# FRA_junctionB_v1.net
KiCad netlist of a schematic drawn in EAGLE
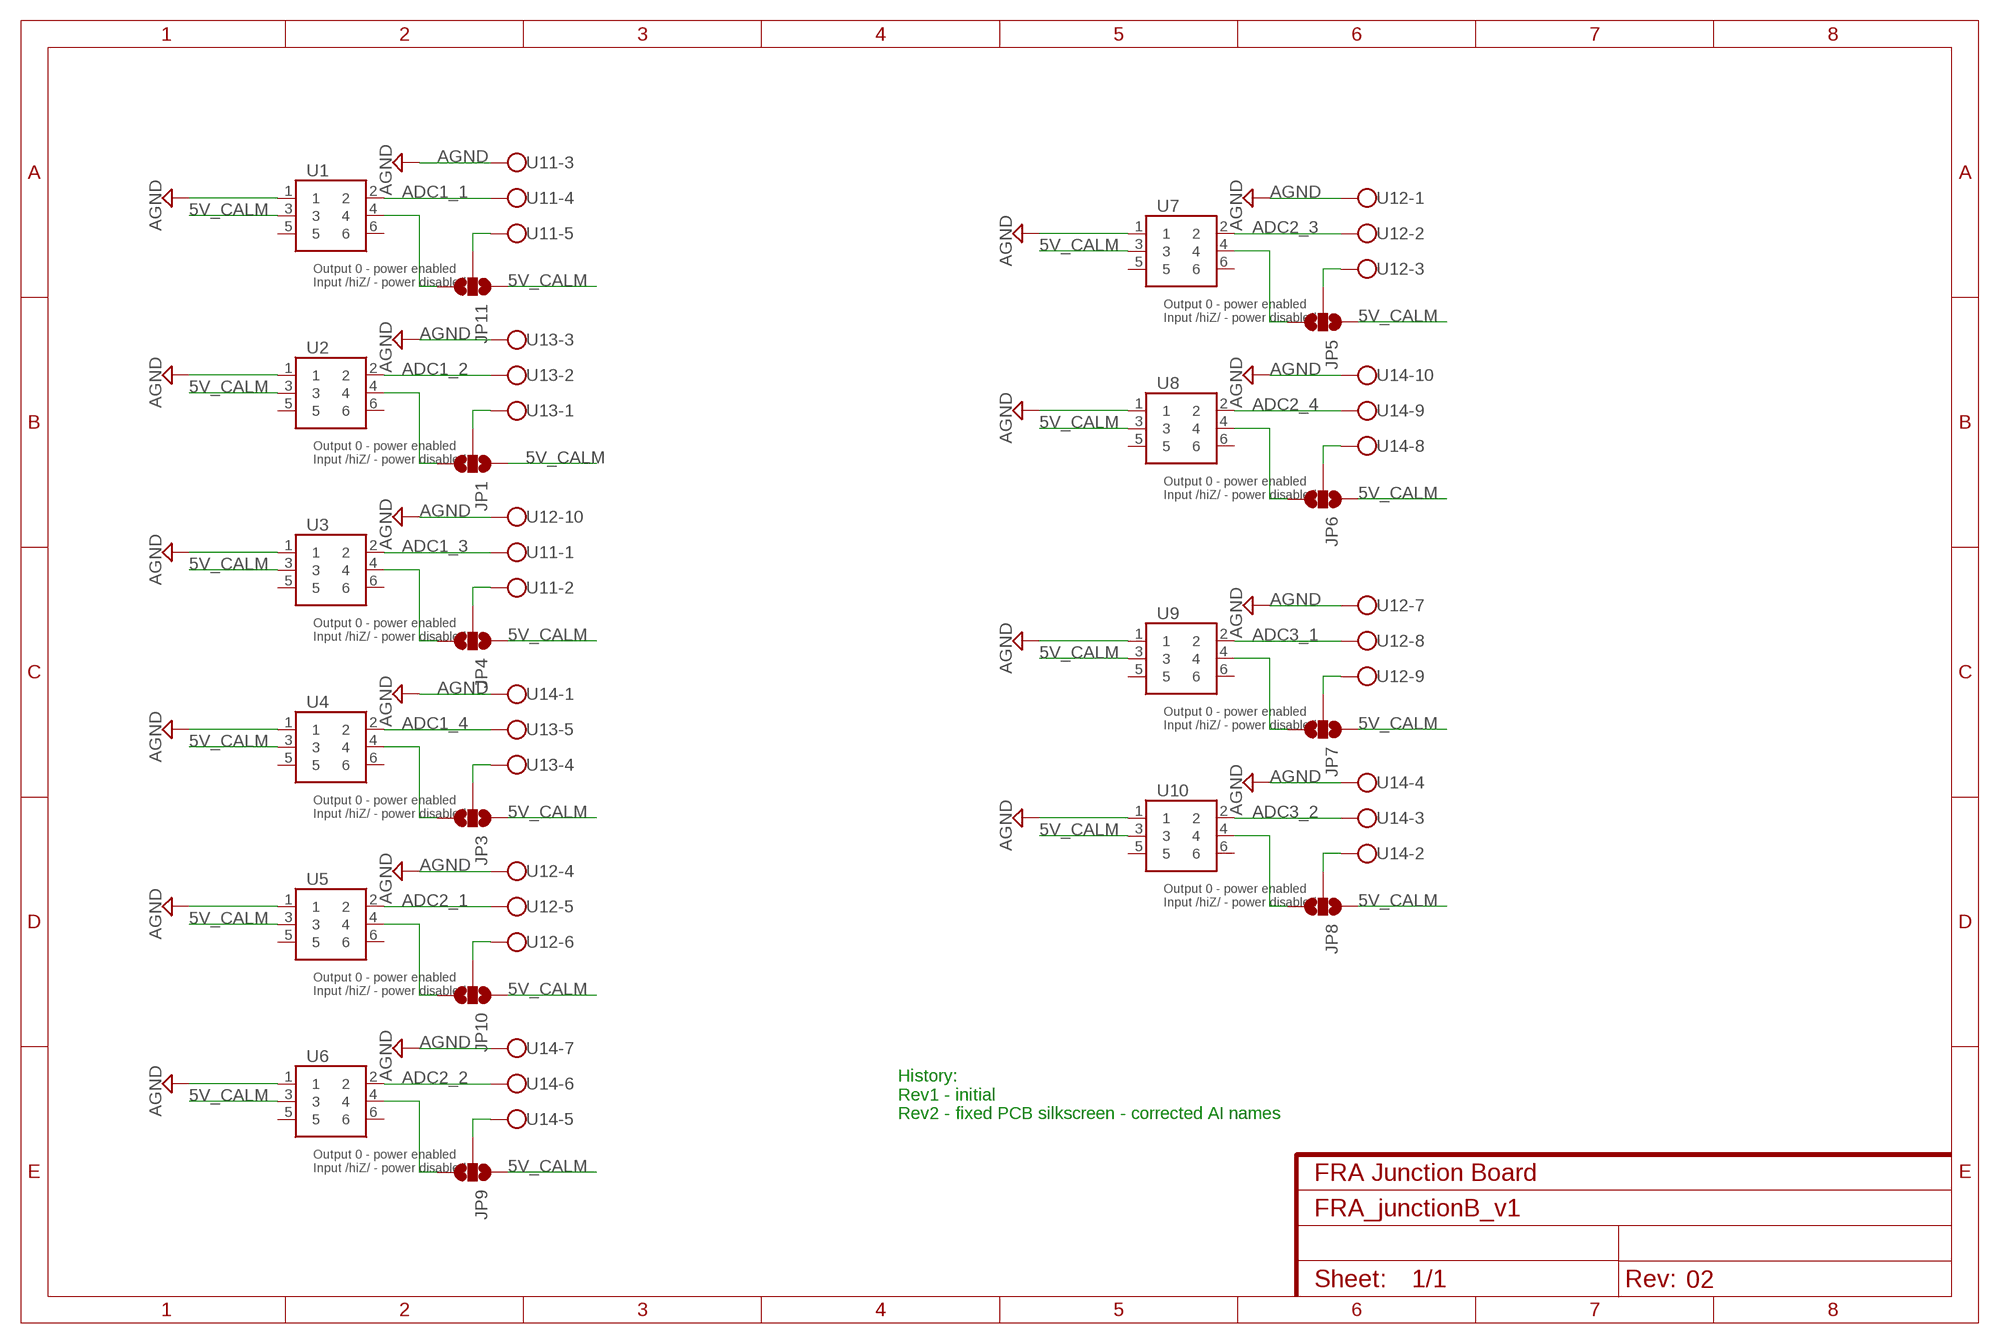
[diagram p0: schematic, sheet 1]

(export (version "E")
  (design (tool "Eeschema 10.0.6"))
  (components
    (comp (ref "JP1")
      (value "JUMPER-SMT_3_NO_NO_SILK")
      (footprint "eagle-import:SMT-JUMPER_3_0-NO_TRACE_NO-SILK")
      (libsource (lib "eagle-import") (part "JUMPER-SMT_3_NO_NO_SILK"))
    )
    (comp (ref "JP3")
      (value "JUMPER-SMT_3_NO_NO_SILK")
      (footprint "eagle-import:SMT-JUMPER_3_0-NO_TRACE_NO-SILK")
      (libsource (lib "eagle-import") (part "JUMPER-SMT_3_NO_NO_SILK"))
    )
    (comp (ref "JP4")
      (value "JUMPER-SMT_3_NO_NO_SILK")
      (footprint "eagle-import:SMT-JUMPER_3_0-NO_TRACE_NO-SILK")
      (libsource (lib "eagle-import") (part "JUMPER-SMT_3_NO_NO_SILK"))
    )
    (comp (ref "JP5")
      (value "JUMPER-SMT_3_NO_NO_SILK")
      (footprint "eagle-import:SMT-JUMPER_3_0-NO_TRACE_NO-SILK")
      (libsource (lib "eagle-import") (part "JUMPER-SMT_3_NO_NO_SILK"))
    )
    (comp (ref "JP6")
      (value "JUMPER-SMT_3_NO_NO_SILK")
      (footprint "eagle-import:SMT-JUMPER_3_0-NO_TRACE_NO-SILK")
      (libsource (lib "eagle-import") (part "JUMPER-SMT_3_NO_NO_SILK"))
    )
    (comp (ref "JP7")
      (value "JUMPER-SMT_3_NO_NO_SILK")
      (footprint "eagle-import:SMT-JUMPER_3_0-NO_TRACE_NO-SILK")
      (libsource (lib "eagle-import") (part "JUMPER-SMT_3_NO_NO_SILK"))
    )
    (comp (ref "JP8")
      (value "JUMPER-SMT_3_NO_NO_SILK")
      (footprint "eagle-import:SMT-JUMPER_3_0-NO_TRACE_NO-SILK")
      (libsource (lib "eagle-import") (part "JUMPER-SMT_3_NO_NO_SILK"))
    )
    (comp (ref "JP9")
      (value "JUMPER-SMT_3_NO_NO_SILK")
      (footprint "eagle-import:SMT-JUMPER_3_0-NO_TRACE_NO-SILK")
      (libsource (lib "eagle-import") (part "JUMPER-SMT_3_NO_NO_SILK"))
    )
    (comp (ref "JP10")
      (value "JUMPER-SMT_3_NO_NO_SILK")
      (footprint "eagle-import:SMT-JUMPER_3_0-NO_TRACE_NO-SILK")
      (libsource (lib "eagle-import") (part "JUMPER-SMT_3_NO_NO_SILK"))
    )
    (comp (ref "JP11")
      (value "JUMPER-SMT_3_NO_NO_SILK")
      (footprint "eagle-import:SMT-JUMPER_3_0-NO_TRACE_NO-SILK")
      (libsource (lib "eagle-import") (part "JUMPER-SMT_3_NO_NO_SILK"))
    )
    (comp (ref "U1")
      (value "SSW-103-01-F-D")
      (footprint "eagle-import:SHDR6W79P254_2X3_813X495X851P")
      (fields (field (name "MOUSER_PART_NUMBER") "200-SSW10301FD") (field (name "PARTNO") "61200621621"))
      (libsource (lib "eagle-import") (part "SSW-103-01-F-D"))
    )
    (comp (ref "U2")
      (value "SSW-103-01-F-D")
      (footprint "eagle-import:SHDR6W79P254_2X3_813X495X851P")
      (fields (field (name "MOUSER_PART_NUMBER") "200-SSW10301FD") (field (name "PARTNO") "61200621621"))
      (libsource (lib "eagle-import") (part "SSW-103-01-F-D"))
    )
    (comp (ref "U3")
      (value "SSW-103-01-F-D")
      (footprint "eagle-import:SHDR6W79P254_2X3_813X495X851P")
      (fields (field (name "MOUSER_PART_NUMBER") "200-SSW10301FD") (field (name "PARTNO") "61200621621"))
      (libsource (lib "eagle-import") (part "SSW-103-01-F-D"))
    )
    (comp (ref "U4")
      (value "SSW-103-01-F-D")
      (footprint "eagle-import:SHDR6W79P254_2X3_813X495X851P")
      (fields (field (name "MOUSER_PART_NUMBER") "200-SSW10301FD") (field (name "PARTNO") "61200621621"))
      (libsource (lib "eagle-import") (part "SSW-103-01-F-D"))
    )
    (comp (ref "U5")
      (value "SSW-103-01-F-D")
      (footprint "eagle-import:SHDR6W79P254_2X3_813X495X851P")
      (fields (field (name "MOUSER_PART_NUMBER") "200-SSW10301FD") (field (name "PARTNO") "61200621621"))
      (libsource (lib "eagle-import") (part "SSW-103-01-F-D"))
    )
    (comp (ref "U6")
      (value "SSW-103-01-F-D")
      (footprint "eagle-import:SHDR6W79P254_2X3_813X495X851P")
      (fields (field (name "MOUSER_PART_NUMBER") "200-SSW10301FD") (field (name "PARTNO") "61200621621"))
      (libsource (lib "eagle-import") (part "SSW-103-01-F-D"))
    )
    (comp (ref "U7")
      (value "SSW-103-01-F-D")
      (footprint "eagle-import:SHDR6W79P254_2X3_813X495X851P")
      (fields (field (name "MOUSER_PART_NUMBER") "200-SSW10301FD") (field (name "PARTNO") "61200621621"))
      (libsource (lib "eagle-import") (part "SSW-103-01-F-D"))
    )
    (comp (ref "U8")
      (value "SSW-103-01-F-D")
      (footprint "eagle-import:SHDR6W79P254_2X3_813X495X851P")
      (fields (field (name "MOUSER_PART_NUMBER") "200-SSW10301FD") (field (name "PARTNO") "61200621621"))
      (libsource (lib "eagle-import") (part "SSW-103-01-F-D"))
    )
    (comp (ref "U9")
      (value "SSW-103-01-F-D")
      (footprint "eagle-import:SHDR6W79P254_2X3_813X495X851P")
      (fields (field (name "MOUSER_PART_NUMBER") "200-SSW10301FD") (field (name "PARTNO") "61200621621"))
      (libsource (lib "eagle-import") (part "SSW-103-01-F-D"))
    )
    (comp (ref "U10")
      (value "SSW-103-01-F-D")
      (footprint "eagle-import:SHDR6W79P254_2X3_813X495X851P")
      (fields (field (name "MOUSER_PART_NUMBER") "200-SSW10301FD") (field (name "PARTNO") "61200621621"))
      (libsource (lib "eagle-import") (part "SSW-103-01-F-D"))
    )
    (comp (ref "U11")
      (value "TB003V-500-P05BE")
      (footprint "eagle-import:TB003V-500-P05BE")
      (libsource (lib "eagle-import") (part "TB003V-500-P05BE"))
    )
    (comp (ref "U12")
      (value "TB003V-500-P10BE")
      (footprint "eagle-import:TB003V-500-P10BE")
      (libsource (lib "eagle-import") (part "TB003V-500-P10BE"))
    )
    (comp (ref "U13")
      (value "TB003V-500-P05BE")
      (footprint "eagle-import:TB003V-500-P05BE")
      (libsource (lib "eagle-import") (part "TB003V-500-P05BE"))
    )
    (comp (ref "U14")
      (value "TB003V-500-P10BE")
      (footprint "eagle-import:TB003V-500-P10BE")
      (libsource (lib "eagle-import") (part "TB003V-500-P10BE"))
    )
  )
  (nets
    (net (code "1") (name "/5V_CALM") (class "Default")
      (node (ref "JP1") (pin "1") (pinfunction "1_1") (pintype "passive"))
      (node (ref "JP10") (pin "1") (pinfunction "1_1") (pintype "passive"))
      (node (ref "JP11") (pin "1") (pinfunction "1_1") (pintype "passive"))
      (node (ref "JP3") (pin "1") (pinfunction "1_1") (pintype "passive"))
      (node (ref "JP4") (pin "1") (pinfunction "1_1") (pintype "passive"))
      (node (ref "JP5") (pin "1") (pinfunction "1_1") (pintype "passive"))
      (node (ref "JP6") (pin "1") (pinfunction "1_1") (pintype "passive"))
      (node (ref "JP7") (pin "1") (pinfunction "1_1") (pintype "passive"))
      (node (ref "JP8") (pin "1") (pinfunction "1_1") (pintype "passive"))
      (node (ref "JP9") (pin "1") (pinfunction "1_1") (pintype "passive"))
      (node (ref "U1") (pin "3") (pinfunction "3_3") (pintype "bidirectional"))
      (node (ref "U10") (pin "3") (pinfunction "3_3") (pintype "bidirectional"))
      (node (ref "U2") (pin "3") (pinfunction "3_3") (pintype "bidirectional"))
      (node (ref "U3") (pin "3") (pinfunction "3_3") (pintype "bidirectional"))
      (node (ref "U4") (pin "3") (pinfunction "3_3") (pintype "bidirectional"))
      (node (ref "U5") (pin "3") (pinfunction "3_3") (pintype "bidirectional"))
      (node (ref "U6") (pin "3") (pinfunction "3_3") (pintype "bidirectional"))
      (node (ref "U7") (pin "3") (pinfunction "3_3") (pintype "bidirectional"))
      (node (ref "U8") (pin "3") (pinfunction "3_3") (pintype "bidirectional"))
      (node (ref "U9") (pin "3") (pinfunction "3_3") (pintype "bidirectional"))
    )
    (net (code "2") (name "/ADC1_1") (class "Default")
      (node (ref "U1") (pin "2") (pinfunction "2_2") (pintype "bidirectional"))
      (node (ref "U11") (pin "4") (pinfunction "KL_4") (pintype "passive"))
    )
    (net (code "3") (name "/ADC1_2") (class "Default")
      (node (ref "U13") (pin "2") (pinfunction "KL_2") (pintype "passive"))
      (node (ref "U2") (pin "2") (pinfunction "2_2") (pintype "bidirectional"))
    )
    (net (code "4") (name "/ADC1_3") (class "Default")
      (node (ref "U11") (pin "1") (pinfunction "KL_1") (pintype "passive"))
      (node (ref "U3") (pin "2") (pinfunction "2_2") (pintype "bidirectional"))
    )
    (net (code "5") (name "/ADC1_4") (class "Default")
      (node (ref "U13") (pin "5") (pinfunction "KL_5") (pintype "passive"))
      (node (ref "U4") (pin "2") (pinfunction "2_2") (pintype "bidirectional"))
    )
    (net (code "6") (name "/ADC2_1") (class "Default")
      (node (ref "U12") (pin "5") (pinfunction "KL_5") (pintype "passive"))
      (node (ref "U5") (pin "2") (pinfunction "2_2") (pintype "bidirectional"))
    )
    (net (code "7") (name "/ADC2_2") (class "Default")
      (node (ref "U14") (pin "6") (pinfunction "KL_6") (pintype "passive"))
      (node (ref "U6") (pin "2") (pinfunction "2_2") (pintype "bidirectional"))
    )
    (net (code "8") (name "/ADC2_3") (class "Default")
      (node (ref "U12") (pin "2") (pinfunction "KL_2") (pintype "passive"))
      (node (ref "U7") (pin "2") (pinfunction "2_2") (pintype "bidirectional"))
    )
    (net (code "9") (name "/ADC2_4") (class "Default")
      (node (ref "U14") (pin "9") (pinfunction "KL_9") (pintype "passive"))
      (node (ref "U8") (pin "2") (pinfunction "2_2") (pintype "bidirectional"))
    )
    (net (code "10") (name "/ADC3_1") (class "Default")
      (node (ref "U12") (pin "8") (pinfunction "KL_8") (pintype "passive"))
      (node (ref "U9") (pin "2") (pinfunction "2_2") (pintype "bidirectional"))
    )
    (net (code "11") (name "/ADC3_2") (class "Default")
      (node (ref "U10") (pin "2") (pinfunction "2_2") (pintype "bidirectional"))
      (node (ref "U14") (pin "3") (pinfunction "KL_3") (pintype "passive"))
    )
    (net (code "12") (name "AGND") (class "Default")
      (node (ref "U1") (pin "1") (pinfunction "1_1") (pintype "bidirectional"))
      (node (ref "U10") (pin "1") (pinfunction "1_1") (pintype "bidirectional"))
      (node (ref "U11") (pin "3") (pinfunction "KL_3") (pintype "passive"))
      (node (ref "U12") (pin "1") (pinfunction "KL_1") (pintype "passive"))
      (node (ref "U12") (pin "10") (pinfunction "KL_10") (pintype "passive"))
      (node (ref "U12") (pin "4") (pinfunction "KL_4") (pintype "passive"))
      (node (ref "U12") (pin "7") (pinfunction "KL_7") (pintype "passive"))
      (node (ref "U13") (pin "3") (pinfunction "KL_3") (pintype "passive"))
      (node (ref "U14") (pin "1") (pinfunction "KL_1") (pintype "passive"))
      (node (ref "U14") (pin "10") (pinfunction "KL_10") (pintype "passive"))
      (node (ref "U14") (pin "4") (pinfunction "KL_4") (pintype "passive"))
      (node (ref "U14") (pin "7") (pinfunction "KL_7") (pintype "passive"))
      (node (ref "U2") (pin "1") (pinfunction "1_1") (pintype "bidirectional"))
      (node (ref "U3") (pin "1") (pinfunction "1_1") (pintype "bidirectional"))
      (node (ref "U4") (pin "1") (pinfunction "1_1") (pintype "bidirectional"))
      (node (ref "U5") (pin "1") (pinfunction "1_1") (pintype "bidirectional"))
      (node (ref "U6") (pin "1") (pinfunction "1_1") (pintype "bidirectional"))
      (node (ref "U7") (pin "1") (pinfunction "1_1") (pintype "bidirectional"))
      (node (ref "U8") (pin "1") (pinfunction "1_1") (pintype "bidirectional"))
      (node (ref "U9") (pin "1") (pinfunction "1_1") (pintype "bidirectional"))
    )
    (net (code "13") (name "Net-(JP1-Pad3)") (class "Default")
      (node (ref "JP1") (pin "3") (pinfunction "3_3") (pintype "passive"))
      (node (ref "U2") (pin "4") (pinfunction "4_4") (pintype "bidirectional"))
    )
    (net (code "14") (name "Net-(JP3-Pad3)") (class "Default")
      (node (ref "JP3") (pin "3") (pinfunction "3_3") (pintype "passive"))
      (node (ref "U4") (pin "4") (pinfunction "4_4") (pintype "bidirectional"))
    )
    (net (code "15") (name "Net-(JP4-Pad3)") (class "Default")
      (node (ref "JP4") (pin "3") (pinfunction "3_3") (pintype "passive"))
      (node (ref "U3") (pin "4") (pinfunction "4_4") (pintype "bidirectional"))
    )
    (net (code "16") (name "Net-(JP5-Pad3)") (class "Default")
      (node (ref "JP5") (pin "3") (pinfunction "3_3") (pintype "passive"))
      (node (ref "U7") (pin "4") (pinfunction "4_4") (pintype "bidirectional"))
    )
    (net (code "17") (name "Net-(JP6-Pad3)") (class "Default")
      (node (ref "JP6") (pin "3") (pinfunction "3_3") (pintype "passive"))
      (node (ref "U8") (pin "4") (pinfunction "4_4") (pintype "bidirectional"))
    )
    (net (code "18") (name "Net-(JP7-Pad3)") (class "Default")
      (node (ref "JP7") (pin "3") (pinfunction "3_3") (pintype "passive"))
      (node (ref "U9") (pin "4") (pinfunction "4_4") (pintype "bidirectional"))
    )
    (net (code "19") (name "Net-(JP8-Pad3)") (class "Default")
      (node (ref "JP8") (pin "3") (pinfunction "3_3") (pintype "passive"))
      (node (ref "U10") (pin "4") (pinfunction "4_4") (pintype "bidirectional"))
    )
    (net (code "20") (name "Net-(JP9-Pad3)") (class "Default")
      (node (ref "JP9") (pin "3") (pinfunction "3_3") (pintype "passive"))
      (node (ref "U6") (pin "4") (pinfunction "4_4") (pintype "bidirectional"))
    )
    (net (code "21") (name "Net-(JP10-Pad3)") (class "Default")
      (node (ref "JP10") (pin "3") (pinfunction "3_3") (pintype "passive"))
      (node (ref "U5") (pin "4") (pinfunction "4_4") (pintype "bidirectional"))
    )
    (net (code "22") (name "Net-(JP11-Pad3)") (class "Default")
      (node (ref "JP11") (pin "3") (pinfunction "3_3") (pintype "passive"))
      (node (ref "U1") (pin "4") (pinfunction "4_4") (pintype "bidirectional"))
    )
    (net (code "23") (name "Net-(U11B-KL)") (class "Default")
      (node (ref "JP4") (pin "2") (pinfunction "2_2") (pintype "passive"))
      (node (ref "U11") (pin "2") (pinfunction "KL_2") (pintype "passive"))
    )
    (net (code "24") (name "Net-(U11E-KL)") (class "Default")
      (node (ref "JP11") (pin "2") (pinfunction "2_2") (pintype "passive"))
      (node (ref "U11") (pin "5") (pinfunction "KL_5") (pintype "passive"))
    )
    (net (code "25") (name "Net-(U12D-KL)") (class "Default")
      (node (ref "JP5") (pin "2") (pinfunction "2_2") (pintype "passive"))
      (node (ref "U12") (pin "3") (pinfunction "KL_3") (pintype "passive"))
    )
    (net (code "26") (name "Net-(U12G-KL)") (class "Default")
      (node (ref "JP10") (pin "2") (pinfunction "2_2") (pintype "passive"))
      (node (ref "U12") (pin "6") (pinfunction "KL_6") (pintype "passive"))
    )
    (net (code "27") (name "Net-(U12J-KL)") (class "Default")
      (node (ref "JP7") (pin "2") (pinfunction "2_2") (pintype "passive"))
      (node (ref "U12") (pin "9") (pinfunction "KL_9") (pintype "passive"))
    )
    (net (code "28") (name "Net-(U13A-KL)") (class "Default")
      (node (ref "JP1") (pin "2") (pinfunction "2_2") (pintype "passive"))
      (node (ref "U13") (pin "1") (pinfunction "KL_1") (pintype "passive"))
    )
    (net (code "29") (name "Net-(U13D-KL)") (class "Default")
      (node (ref "JP3") (pin "2") (pinfunction "2_2") (pintype "passive"))
      (node (ref "U13") (pin "4") (pinfunction "KL_4") (pintype "passive"))
    )
    (net (code "30") (name "Net-(U14C-KL)") (class "Default")
      (node (ref "JP8") (pin "2") (pinfunction "2_2") (pintype "passive"))
      (node (ref "U14") (pin "2") (pinfunction "KL_2") (pintype "passive"))
    )
    (net (code "31") (name "Net-(U14F-KL)") (class "Default")
      (node (ref "JP9") (pin "2") (pinfunction "2_2") (pintype "passive"))
      (node (ref "U14") (pin "5") (pinfunction "KL_5") (pintype "passive"))
    )
    (net (code "32") (name "Net-(U14I-KL)") (class "Default")
      (node (ref "JP6") (pin "2") (pinfunction "2_2") (pintype "passive"))
      (node (ref "U14") (pin "8") (pinfunction "KL_8") (pintype "passive"))
    )
    (net (code "33") (name "unconnected-(U1-Pad5)") (class "Default")
      (node (ref "U1") (pin "5") (pinfunction "5_5") (pintype "bidirectional"))
    )
    (net (code "34") (name "unconnected-(U1-Pad6)") (class "Default")
      (node (ref "U1") (pin "6") (pinfunction "6_6") (pintype "bidirectional"))
    )
    (net (code "35") (name "unconnected-(U2-Pad5)") (class "Default")
      (node (ref "U2") (pin "5") (pinfunction "5_5") (pintype "bidirectional"))
    )
    (net (code "36") (name "unconnected-(U2-Pad6)") (class "Default")
      (node (ref "U2") (pin "6") (pinfunction "6_6") (pintype "bidirectional"))
    )
    (net (code "37") (name "unconnected-(U3-Pad5)") (class "Default")
      (node (ref "U3") (pin "5") (pinfunction "5_5") (pintype "bidirectional"))
    )
    (net (code "38") (name "unconnected-(U3-Pad6)") (class "Default")
      (node (ref "U3") (pin "6") (pinfunction "6_6") (pintype "bidirectional"))
    )
    (net (code "39") (name "unconnected-(U4-Pad5)") (class "Default")
      (node (ref "U4") (pin "5") (pinfunction "5_5") (pintype "bidirectional"))
    )
    (net (code "40") (name "unconnected-(U4-Pad6)") (class "Default")
      (node (ref "U4") (pin "6") (pinfunction "6_6") (pintype "bidirectional"))
    )
    (net (code "41") (name "unconnected-(U5-Pad5)") (class "Default")
      (node (ref "U5") (pin "5") (pinfunction "5_5") (pintype "bidirectional"))
    )
    (net (code "42") (name "unconnected-(U5-Pad6)") (class "Default")
      (node (ref "U5") (pin "6") (pinfunction "6_6") (pintype "bidirectional"))
    )
    (net (code "43") (name "unconnected-(U6-Pad5)") (class "Default")
      (node (ref "U6") (pin "5") (pinfunction "5_5") (pintype "bidirectional"))
    )
    (net (code "44") (name "unconnected-(U6-Pad6)") (class "Default")
      (node (ref "U6") (pin "6") (pinfunction "6_6") (pintype "bidirectional"))
    )
    (net (code "45") (name "unconnected-(U7-Pad5)") (class "Default")
      (node (ref "U7") (pin "5") (pinfunction "5_5") (pintype "bidirectional"))
    )
    (net (code "46") (name "unconnected-(U7-Pad6)") (class "Default")
      (node (ref "U7") (pin "6") (pinfunction "6_6") (pintype "bidirectional"))
    )
    (net (code "47") (name "unconnected-(U8-Pad5)") (class "Default")
      (node (ref "U8") (pin "5") (pinfunction "5_5") (pintype "bidirectional"))
    )
    (net (code "48") (name "unconnected-(U8-Pad6)") (class "Default")
      (node (ref "U8") (pin "6") (pinfunction "6_6") (pintype "bidirectional"))
    )
    (net (code "49") (name "unconnected-(U9-Pad5)") (class "Default")
      (node (ref "U9") (pin "5") (pinfunction "5_5") (pintype "bidirectional"))
    )
    (net (code "50") (name "unconnected-(U9-Pad6)") (class "Default")
      (node (ref "U9") (pin "6") (pinfunction "6_6") (pintype "bidirectional"))
    )
    (net (code "51") (name "unconnected-(U10-Pad5)") (class "Default")
      (node (ref "U10") (pin "5") (pinfunction "5_5") (pintype "bidirectional"))
    )
    (net (code "52") (name "unconnected-(U10-Pad6)") (class "Default")
      (node (ref "U10") (pin "6") (pinfunction "6_6") (pintype "bidirectional"))
    )
  )
)
